# Papra_v0_6.net
KiCad netlist of a schematic drawn in EAGLE
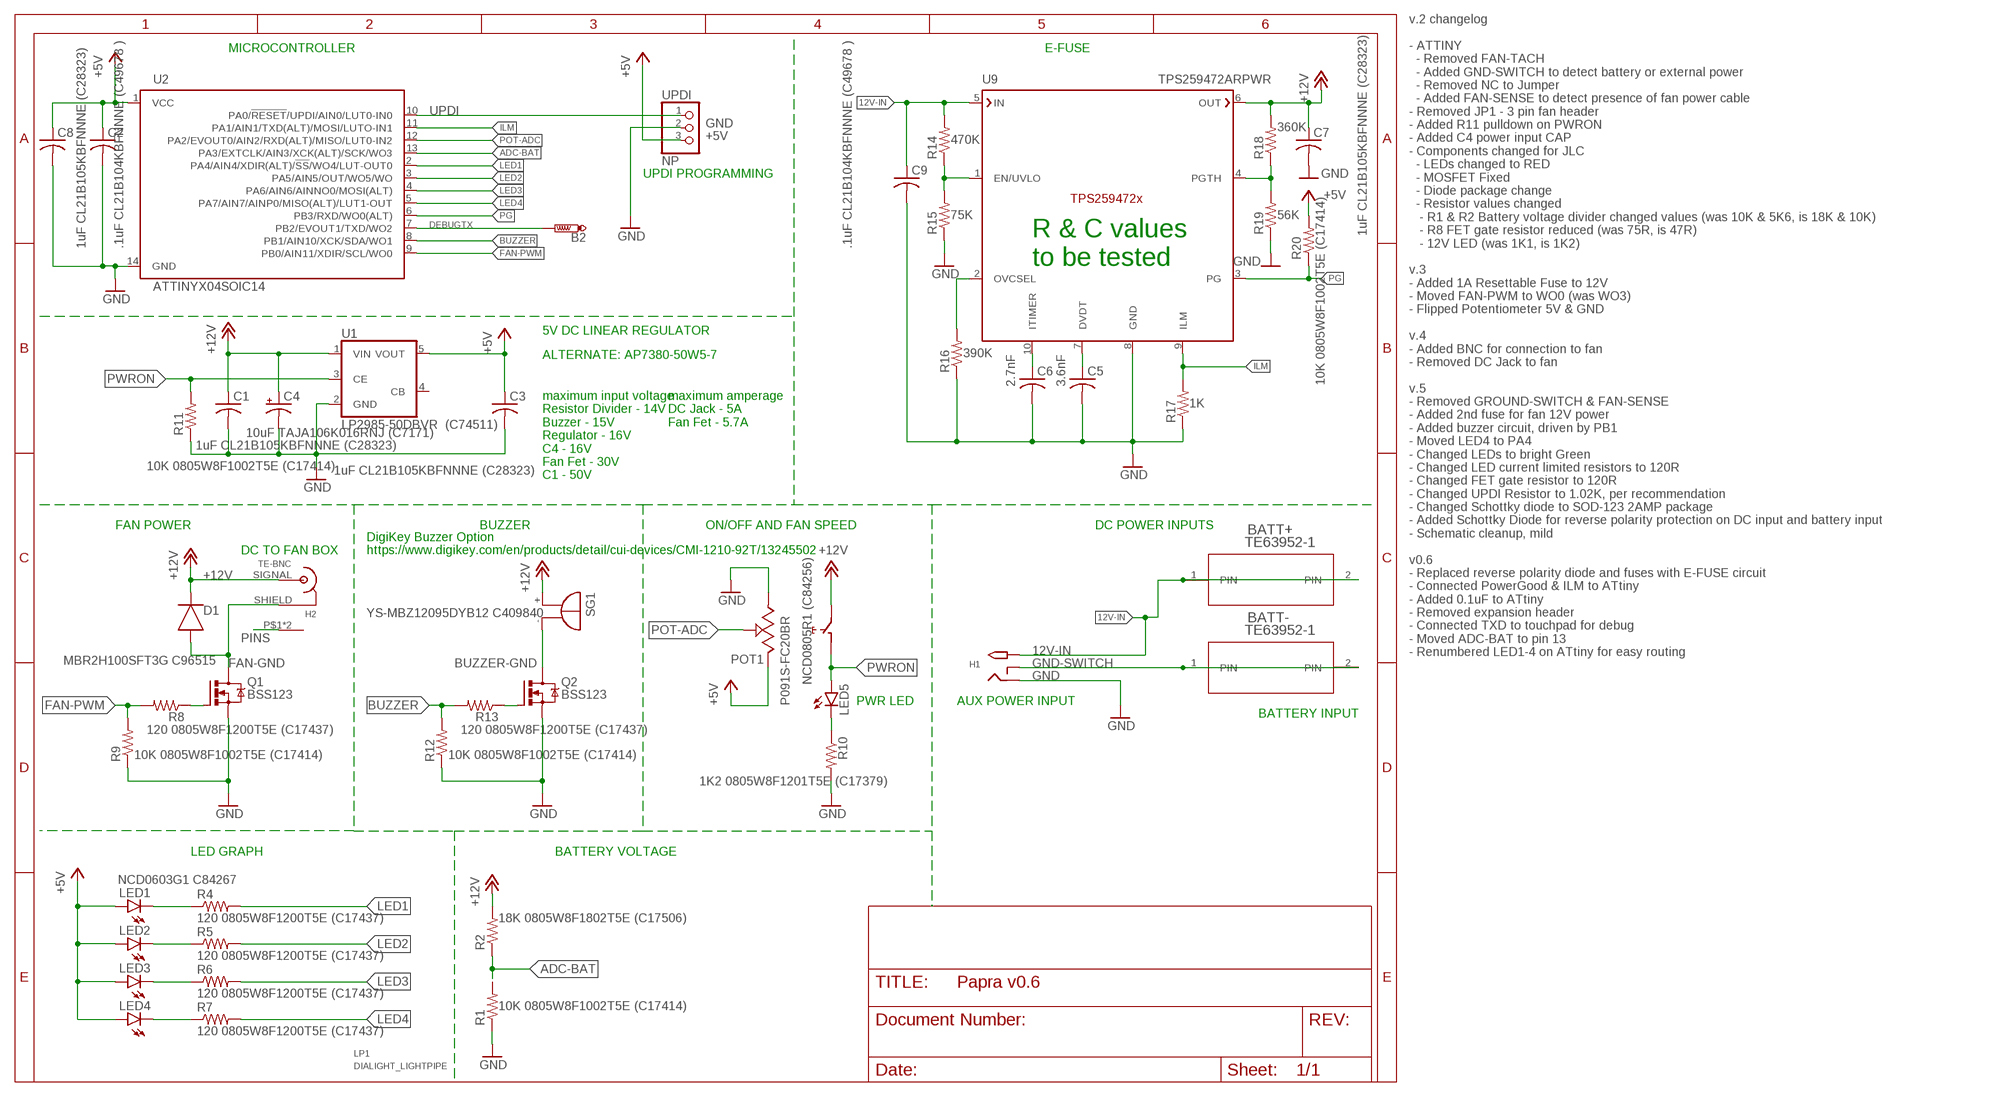
[diagram p0: schematic, sheet 1]

(export (version "E")
  (design (tool "Eeschema 10.0.6"))
  (components
    (comp (ref "B2")
      (value "PTR1PAD1-13")
      (footprint "eagle-import:P1-13")
      (libsource (lib "eagle-import") (part "PTR1PAD1-13"))
    )
    (comp (ref "BATT+")
      (value "TE63952-1")
      (footprint "eagle-import:TE63952-1")
      (libsource (lib "eagle-import") (part "TE63952-1"))
    )
    (comp (ref "BATT-")
      (value "TE63952-1")
      (footprint "eagle-import:TE63952-1")
      (libsource (lib "eagle-import") (part "TE63952-1"))
    )
    (comp (ref "C1")
      (value "1uF CL21B105KBFNNNE (C28323)")
      (footprint "eagle-import:C0805")
      (libsource (lib "eagle-import") (part "C-USC0805"))
    )
    (comp (ref "C2")
      (value ".1uF CL21B104KBFNNNE (C49678 )")
      (footprint "eagle-import:C0805")
      (libsource (lib "eagle-import") (part "C-USC0805"))
    )
    (comp (ref "C3")
      (value "1uF CL21B105KBFNNNE (C28323)")
      (footprint "eagle-import:C0805")
      (libsource (lib "eagle-import") (part "C-USC0805"))
    )
    (comp (ref "C4")
      (value "10uF TAJA106K016RNJ (C7171)")
      (footprint "eagle-import:A_3216-18R")
      (libsource (lib "eagle-import") (part "CPOL-USA/3216-18R"))
    )
    (comp (ref "C5")
      (value "3.6nF")
      (footprint "eagle-import:C0805")
      (libsource (lib "eagle-import") (part "C-USC0805"))
    )
    (comp (ref "C6")
      (value "2.7nF")
      (footprint "eagle-import:C0805")
      (libsource (lib "eagle-import") (part "C-USC0805"))
    )
    (comp (ref "C7")
      (value "1uF CL21B105KBFNNNE (C28323)")
      (footprint "eagle-import:C0805")
      (libsource (lib "eagle-import") (part "C-USC0805"))
    )
    (comp (ref "C8")
      (value "1uF CL21B105KBFNNNE (C28323)")
      (footprint "eagle-import:C0805")
      (libsource (lib "eagle-import") (part "C-USC0805"))
    )
    (comp (ref "C9")
      (value ".1uF CL21B104KBFNNNE (C49678 )")
      (footprint "eagle-import:C0805")
      (libsource (lib "eagle-import") (part "C-USC0805"))
    )
    (comp (ref "D1")
      (value "MBR2H100SFT3G C96515")
      (footprint "eagle-import:SODFL3718X115")
      (libsource (lib "eagle-import") (part "DIODEDO-219-AB(SOD123F)_"))
    )
    (comp (ref "H1")
      (value "M-CUI-PJ-066A")
      (footprint "eagle-import:DCJACK-PJ-066A")
      (libsource (lib "eagle-import") (part "PJ-066A"))
    )
    (comp (ref "H2")
      (value "TE-BNC")
      (footprint "eagle-import:TE-BNC")
      (libsource (lib "eagle-import") (part "TE-BNC"))
    )
    (comp (ref "LED1")
      (value "NCD0603G1 C84267")
      (footprint "eagle-import:CHIPLED_0805")
      (libsource (lib "eagle-import") (part "LEDCHIPLED_0805"))
    )
    (comp (ref "LED2")
      (value "NCD0603G1 C84267")
      (footprint "eagle-import:CHIPLED_0805")
      (libsource (lib "eagle-import") (part "LEDCHIPLED_0805"))
    )
    (comp (ref "LED3")
      (value "NCD0603G1 C84267")
      (footprint "eagle-import:CHIPLED_0805")
      (libsource (lib "eagle-import") (part "LEDCHIPLED_0805"))
    )
    (comp (ref "LED4")
      (value "NCD0603G1 C84267")
      (footprint "eagle-import:CHIPLED_0805")
      (libsource (lib "eagle-import") (part "LEDCHIPLED_0805"))
    )
    (comp (ref "LED5")
      (value "NCD0805R1 (C84256)")
      (footprint "eagle-import:CHIPLED_0805")
      (libsource (lib "eagle-import") (part "LEDCHIPLED_0805"))
    )
    (comp (ref "LP1")
      (value "DIALIGHT_LIGHTPIPE")
      (footprint "eagle-import:DIALIGHT_5151020F__LEDS")
      (libsource (lib "eagle-import") (part "DIALIGHT_LIGHTPIPE"))
    )
    (comp (ref "POT1")
      (value "P091S-FC20BR")
      (footprint "eagle-import:P091S-FC20BR")
      (libsource (lib "eagle-import") (part "P091S-FC20BR"))
    )
    (comp (ref "Q1")
      (value "BSS123")
      (footprint "eagle-import:SOT23")
      (fields (field (name "MANUFACTURER") "ON Semiconductor") (field (name "MPN") "BSS123L"))
      (libsource (lib "eagle-import") (part "NMOSFET_-SOT23BSS123"))
    )
    (comp (ref "Q2")
      (value "BSS123")
      (footprint "eagle-import:SOT23")
      (fields (field (name "MANUFACTURER") "ON Semiconductor") (field (name "MPN") "BSS123L"))
      (libsource (lib "eagle-import") (part "NMOSFET_-SOT23BSS123"))
    )
    (comp (ref "R1")
      (value "10K 0805W8F1002T5E (C17414)")
      (footprint "eagle-import:R0805")
      (libsource (lib "eagle-import") (part "R-US_R0805"))
    )
    (comp (ref "R2")
      (value "18K 0805W8F1802T5E (C17506)")
      (footprint "eagle-import:R0805")
      (libsource (lib "eagle-import") (part "R-US_R0805"))
    )
    (comp (ref "R4")
      (value "120 0805W8F1200T5E (C17437)")
      (footprint "eagle-import:R0805")
      (libsource (lib "eagle-import") (part "R-US_R0805"))
    )
    (comp (ref "R5")
      (value "120 0805W8F1200T5E (C17437)")
      (footprint "eagle-import:R0805")
      (libsource (lib "eagle-import") (part "R-US_R0805"))
    )
    (comp (ref "R6")
      (value "120 0805W8F1200T5E (C17437)")
      (footprint "eagle-import:R0805")
      (libsource (lib "eagle-import") (part "R-US_R0805"))
    )
    (comp (ref "R7")
      (value "120 0805W8F1200T5E (C17437)")
      (footprint "eagle-import:R0805")
      (libsource (lib "eagle-import") (part "R-US_R0805"))
    )
    (comp (ref "R8")
      (value "120 0805W8F1200T5E (C17437)")
      (footprint "eagle-import:R0805")
      (libsource (lib "eagle-import") (part "R-US_R0805"))
    )
    (comp (ref "R9")
      (value "10K 0805W8F1002T5E (C17414)")
      (footprint "eagle-import:R0805")
      (libsource (lib "eagle-import") (part "R-US_R0805"))
    )
    (comp (ref "R10")
      (value "1K2 0805W8F1201T5E (C17379)")
      (footprint "eagle-import:R0805")
      (libsource (lib "eagle-import") (part "R-US_R0805"))
    )
    (comp (ref "R11")
      (value "10K 0805W8F1002T5E (C17414)")
      (footprint "eagle-import:R0805")
      (libsource (lib "eagle-import") (part "R-US_R0805"))
    )
    (comp (ref "R12")
      (value "10K 0805W8F1002T5E (C17414)")
      (footprint "eagle-import:R0805")
      (libsource (lib "eagle-import") (part "R-US_R0805"))
    )
    (comp (ref "R13")
      (value "120 0805W8F1200T5E (C17437)")
      (footprint "eagle-import:R0805")
      (libsource (lib "eagle-import") (part "R-US_R0805"))
    )
    (comp (ref "R14")
      (value "470K")
      (footprint "eagle-import:R0805")
      (libsource (lib "eagle-import") (part "R-US_R0805"))
    )
    (comp (ref "R15")
      (value "75K")
      (footprint "eagle-import:R0805")
      (libsource (lib "eagle-import") (part "R-US_R0805"))
    )
    (comp (ref "R16")
      (value "390K")
      (footprint "eagle-import:R0805")
      (libsource (lib "eagle-import") (part "R-US_R0805"))
    )
    (comp (ref "R17")
      (value "1K")
      (footprint "eagle-import:R0805")
      (libsource (lib "eagle-import") (part "R-US_R0805"))
    )
    (comp (ref "R18")
      (value "360K")
      (footprint "eagle-import:R0805")
      (libsource (lib "eagle-import") (part "R-US_R0805"))
    )
    (comp (ref "R19")
      (value "56K")
      (footprint "eagle-import:R0805")
      (libsource (lib "eagle-import") (part "R-US_R0805"))
    )
    (comp (ref "R20")
      (value "10K 0805W8F1002T5E (C17414)")
      (footprint "eagle-import:R0805")
      (libsource (lib "eagle-import") (part "R-US_R0805"))
    )
    (comp (ref "SG1")
      (value "YS-MBZ12095DYB12 C409840")
      (footprint "eagle-import:F_TMB")
      (libsource (lib "eagle-import") (part "F/TMB"))
    )
    (comp (ref "U1")
      (value "LP2985-50DBVR (C74511)")
      (footprint "eagle-import:SOT25")
      (libsource (lib "eagle-import") (part "TS520533"))
    )
    (comp (ref "U2")
      (value "ATTINYX04SOIC14")
      (footprint "eagle-import:SOIC127P600X144-14")
      (libsource (lib "eagle-import") (part "ATTINYX04SOIC14"))
    )
    (comp (ref "U9")
      (value "TPS259472ARPWR")
      (footprint "eagle-import:QFN45P200X200X100-16N")
      (libsource (lib "eagle-import") (part "TPS259472ARPWR"))
    )
    (comp (ref "UPDI")
      (value "NP")
      (footprint "eagle-import:1X03")
      (libsource (lib "eagle-import") (part "PINHD-1X3"))
    )
  )
  (nets
    (net (code "1") (name "+5V") (class "Default")
      (node (ref "C2") (pin "1") (pinfunction "1_1") (pintype "passive"))
      (node (ref "C3") (pin "1") (pinfunction "1_1") (pintype "passive"))
      (node (ref "C8") (pin "1") (pinfunction "1_1") (pintype "passive"))
      (node (ref "LED1") (pin "A") (pinfunction "A_A") (pintype "passive"))
      (node (ref "LED2") (pin "A") (pinfunction "A_A") (pintype "passive"))
      (node (ref "LED3") (pin "A") (pinfunction "A_A") (pintype "passive"))
      (node (ref "LED4") (pin "A") (pinfunction "A_A") (pintype "passive"))
      (node (ref "POT1") (pin "3") (pinfunction "3_3") (pintype "passive"))
      (node (ref "R20") (pin "2") (pinfunction "2_2") (pintype "passive"))
      (node (ref "U1") (pin "5") (pinfunction "VOUT_5") (pintype "passive"))
      (node (ref "U2") (pin "1") (pinfunction "VCC_1") (pintype "power_in"))
      (node (ref "UPDI") (pin "3") (pinfunction "3_3") (pintype "passive"))
    )
    (net (code "2") (name "+12V") (class "Default")
      (node (ref "C1") (pin "1") (pinfunction "1_1") (pintype "passive"))
      (node (ref "C4") (pin "+") (pinfunction "+_+") (pintype "passive"))
      (node (ref "C7") (pin "1") (pinfunction "1_1") (pintype "passive"))
      (node (ref "D1") (pin "1") (pinfunction "C_1") (pintype "passive"))
      (node (ref "H2") (pin "SIGNAL") (pinfunction "P1_SIGNAL") (pintype "passive"))
      (node (ref "POT1") (pin "NO") (pinfunction "5_NO") (pintype "passive"))
      (node (ref "R18") (pin "2") (pinfunction "2_2") (pintype "passive"))
      (node (ref "R2") (pin "2") (pinfunction "2_2") (pintype "passive"))
      (node (ref "SG1") (pin "+") (pinfunction "+_+") (pintype "passive"))
      (node (ref "U1") (pin "1") (pinfunction "VIN_1") (pintype "input"))
      (node (ref "U9") (pin "6") (pinfunction "OUT_6") (pintype "power_in"))
    )
    (net (code "4") (name "/BUZZER-GND") (class "Default")
      (node (ref "Q2") (pin "3") (pinfunction "D_3") (pintype "passive"))
      (node (ref "SG1") (pin "-") (pinfunction "-_-") (pintype "passive"))
    )
    (net (code "5") (name "/DEBUGTX") (class "Default")
      (node (ref "B2") (pin "TP") (pinfunction "TP_TP") (pintype "input"))
      (node (ref "U2") (pin "7") (pinfunction "PB2/EVOUT1/TXD/WO2_7") (pintype "bidirectional"))
    )
    (net (code "6") (name "/FAN-GND") (class "Default")
      (node (ref "D1") (pin "2") (pinfunction "A_2") (pintype "passive"))
      (node (ref "H2") (pin "SHIELD") (pinfunction "P2_SHIELD") (pintype "passive"))
      (node (ref "Q1") (pin "3") (pinfunction "D_3") (pintype "passive"))
    )
    (net (code "7") (name "/GND-SWITCH") (class "Default")
      (node (ref "BATT-") (pin "1") (pinfunction "PIN_1") (pintype "passive"))
      (node (ref "BATT-") (pin "2") (pinfunction "PIN_2") (pintype "passive"))
      (node (ref "H1") (pin "GNDBREAK") (pinfunction "RING_SW_GNDBREAK") (pintype "bidirectional"))
    )
    (net (code "8") (name "/PINS") (class "Default")
      (node (ref "H2") (pin "P$1") (pinfunction "P3_P$1") (pintype "passive"))
      (node (ref "H2") (pin "P$2") (pinfunction "P3_P$2") (pintype "passive"))
    )
    (net (code "9") (name "/UPDI") (class "Default")
      (node (ref "U2") (pin "10") (pinfunction "PA0/~{RESET}/UPDI/AIN0/LUT0-IN0_10") (pintype "bidirectional"))
      (node (ref "UPDI") (pin "1") (pinfunction "1_1") (pintype "passive"))
    )
    (net (code "10") (name "12V-IN") (class "Default")
      (node (ref "BATT+") (pin "1") (pinfunction "PIN_1") (pintype "passive"))
      (node (ref "BATT+") (pin "2") (pinfunction "PIN_2") (pintype "passive"))
      (node (ref "C9") (pin "1") (pinfunction "1_1") (pintype "passive"))
      (node (ref "H1") (pin "PWR") (pinfunction "TIP_PWR") (pintype "bidirectional"))
      (node (ref "R14") (pin "2") (pinfunction "2_2") (pintype "passive"))
      (node (ref "U9") (pin "5") (pinfunction "IN_5") (pintype "power_in"))
    )
    (net (code "11") (name "ADC-BAT") (class "Default")
      (node (ref "R1") (pin "2") (pinfunction "2_2") (pintype "passive"))
      (node (ref "R2") (pin "1") (pinfunction "1_1") (pintype "passive"))
      (node (ref "U2") (pin "13") (pinfunction "PA3/EXTCLK/AIN3/XCK(ALT)/SCK/WO3_13") (pintype "bidirectional"))
    )
    (net (code "12") (name "BUZZER") (class "Default")
      (node (ref "R12") (pin "2") (pinfunction "2_2") (pintype "passive"))
      (node (ref "R13") (pin "2") (pinfunction "2_2") (pintype "passive"))
      (node (ref "U2") (pin "8") (pinfunction "PB1/AIN10/XCK/SDA/WO1_8") (pintype "bidirectional"))
    )
    (net (code "13") (name "FAN-PWM") (class "Default")
      (node (ref "R8") (pin "2") (pinfunction "2_2") (pintype "passive"))
      (node (ref "R9") (pin "2") (pinfunction "2_2") (pintype "passive"))
      (node (ref "U2") (pin "9") (pinfunction "PB0/AIN11/XDIR/SCL/WO0_9") (pintype "bidirectional"))
    )
    (net (code "14") (name "GND") (class "Default")
      (node (ref "C1") (pin "2") (pinfunction "2_2") (pintype "passive"))
      (node (ref "C2") (pin "2") (pinfunction "2_2") (pintype "passive"))
      (node (ref "C3") (pin "2") (pinfunction "2_2") (pintype "passive"))
      (node (ref "C4") (pin "-") (pinfunction "-_-") (pintype "passive"))
      (node (ref "C5") (pin "2") (pinfunction "2_2") (pintype "passive"))
      (node (ref "C6") (pin "2") (pinfunction "2_2") (pintype "passive"))
      (node (ref "C7") (pin "2") (pinfunction "2_2") (pintype "passive"))
      (node (ref "C8") (pin "2") (pinfunction "2_2") (pintype "passive"))
      (node (ref "C9") (pin "2") (pinfunction "2_2") (pintype "passive"))
      (node (ref "H1") (pin "GND") (pinfunction "RING_GND") (pintype "bidirectional"))
      (node (ref "POT1") (pin "1") (pinfunction "1_1") (pintype "passive"))
      (node (ref "Q1") (pin "2") (pinfunction "S_2") (pintype "passive"))
      (node (ref "Q2") (pin "2") (pinfunction "S_2") (pintype "passive"))
      (node (ref "R1") (pin "1") (pinfunction "1_1") (pintype "passive"))
      (node (ref "R10") (pin "2") (pinfunction "2_2") (pintype "passive"))
      (node (ref "R11") (pin "1") (pinfunction "1_1") (pintype "passive"))
      (node (ref "R12") (pin "1") (pinfunction "1_1") (pintype "passive"))
      (node (ref "R15") (pin "1") (pinfunction "1_1") (pintype "passive"))
      (node (ref "R16") (pin "1") (pinfunction "1_1") (pintype "passive"))
      (node (ref "R17") (pin "1") (pinfunction "1_1") (pintype "passive"))
      (node (ref "R19") (pin "1") (pinfunction "1_1") (pintype "passive"))
      (node (ref "R9") (pin "1") (pinfunction "1_1") (pintype "passive"))
      (node (ref "U1") (pin "2") (pinfunction "GND_2") (pintype "passive"))
      (node (ref "U2") (pin "14") (pinfunction "GND_14") (pintype "power_in"))
      (node (ref "U9") (pin "8") (pinfunction "GND_8") (pintype "power_in"))
      (node (ref "UPDI") (pin "2") (pinfunction "2_2") (pintype "passive"))
    )
    (net (code "15") (name "ILM") (class "Default")
      (node (ref "R17") (pin "2") (pinfunction "2_2") (pintype "passive"))
      (node (ref "U2") (pin "11") (pinfunction "PA1/AIN1/TXD(ALT)/MOSI/LUTO-IN1_11") (pintype "bidirectional"))
      (node (ref "U9") (pin "9") (pinfunction "ILM_9") (pintype "output"))
    )
    (net (code "16") (name "LED1") (class "Default")
      (node (ref "R4") (pin "2") (pinfunction "2_2") (pintype "passive"))
      (node (ref "U2") (pin "2") (pinfunction "PA4/AIN4/XDIR(ALT)/~{SS}/WO4/LUT-OUT0_2") (pintype "bidirectional"))
    )
    (net (code "17") (name "LED2") (class "Default")
      (node (ref "R5") (pin "2") (pinfunction "2_2") (pintype "passive"))
      (node (ref "U2") (pin "3") (pinfunction "PA5/AIN5/OUT/WO5/WO_3") (pintype "bidirectional"))
    )
    (net (code "18") (name "LED3") (class "Default")
      (node (ref "R6") (pin "2") (pinfunction "2_2") (pintype "passive"))
      (node (ref "U2") (pin "4") (pinfunction "PA6/AIN6/AINNO0/MOSI(ALT)_4") (pintype "bidirectional"))
    )
    (net (code "19") (name "LED4") (class "Default")
      (node (ref "R7") (pin "2") (pinfunction "2_2") (pintype "passive"))
      (node (ref "U2") (pin "5") (pinfunction "PA7/AIN7/AINP0/MISO(ALT)/LUT1-OUT_5") (pintype "bidirectional"))
    )
    (net (code "20") (name "Net-(LED1-PadC)") (class "Default")
      (node (ref "LED1") (pin "C") (pinfunction "C_C") (pintype "passive"))
      (node (ref "R4") (pin "1") (pinfunction "1_1") (pintype "passive"))
    )
    (net (code "21") (name "Net-(LED2-PadC)") (class "Default")
      (node (ref "LED2") (pin "C") (pinfunction "C_C") (pintype "passive"))
      (node (ref "R5") (pin "1") (pinfunction "1_1") (pintype "passive"))
    )
    (net (code "22") (name "Net-(LED3-PadC)") (class "Default")
      (node (ref "LED3") (pin "C") (pinfunction "C_C") (pintype "passive"))
      (node (ref "R6") (pin "1") (pinfunction "1_1") (pintype "passive"))
    )
    (net (code "23") (name "Net-(LED4-PadC)") (class "Default")
      (node (ref "LED4") (pin "C") (pinfunction "C_C") (pintype "passive"))
      (node (ref "R7") (pin "1") (pinfunction "1_1") (pintype "passive"))
    )
    (net (code "24") (name "Net-(LED5-PadC)") (class "Default")
      (node (ref "LED5") (pin "C") (pinfunction "C_C") (pintype "passive"))
      (node (ref "R10") (pin "1") (pinfunction "1_1") (pintype "passive"))
    )
    (net (code "25") (name "Net-(Q1-G)") (class "Default")
      (node (ref "Q1") (pin "1") (pinfunction "G_1") (pintype "passive"))
      (node (ref "R8") (pin "1") (pinfunction "1_1") (pintype "passive"))
    )
    (net (code "26") (name "Net-(Q2-G)") (class "Default")
      (node (ref "Q2") (pin "1") (pinfunction "G_1") (pintype "passive"))
      (node (ref "R13") (pin "1") (pinfunction "1_1") (pintype "passive"))
    )
    (net (code "27") (name "Net-(U9-DVDT)") (class "Default")
      (node (ref "C5") (pin "1") (pinfunction "1_1") (pintype "passive"))
      (node (ref "U9") (pin "7") (pinfunction "DVDT_7") (pintype "output"))
    )
    (net (code "28") (name "Net-(U9-EN{slash}UVLO)") (class "Default")
      (node (ref "R14") (pin "1") (pinfunction "1_1") (pintype "passive"))
      (node (ref "R15") (pin "2") (pinfunction "2_2") (pintype "passive"))
      (node (ref "U9") (pin "1") (pinfunction "EN/UVLO_1") (pintype "input"))
    )
    (net (code "29") (name "Net-(U9-ITIMER)") (class "Default")
      (node (ref "C6") (pin "1") (pinfunction "1_1") (pintype "passive"))
      (node (ref "U9") (pin "10") (pinfunction "ITIMER_10") (pintype "output"))
    )
    (net (code "30") (name "Net-(U9-OVCSEL)") (class "Default")
      (node (ref "R16") (pin "2") (pinfunction "2_2") (pintype "passive"))
      (node (ref "U9") (pin "2") (pinfunction "OVCSEL_2") (pintype "input"))
    )
    (net (code "31") (name "Net-(U9-PGTH)") (class "Default")
      (node (ref "R18") (pin "1") (pinfunction "1_1") (pintype "passive"))
      (node (ref "R19") (pin "2") (pinfunction "2_2") (pintype "passive"))
      (node (ref "U9") (pin "4") (pinfunction "PGTH_4") (pintype "input"))
    )
    (net (code "32") (name "PG") (class "Default")
      (node (ref "R20") (pin "1") (pinfunction "1_1") (pintype "passive"))
      (node (ref "U2") (pin "6") (pinfunction "PB3/RXD/WO0(ALT)_6") (pintype "bidirectional"))
      (node (ref "U9") (pin "3") (pinfunction "PG_3") (pintype "output"))
    )
    (net (code "33") (name "POT-ADC") (class "Default")
      (node (ref "POT1") (pin "2") (pinfunction "2_2") (pintype "passive"))
      (node (ref "U2") (pin "12") (pinfunction "PA2/EVOUT0/AIN2/RXD(ALT)/MISO/LUT0-IN2_12") (pintype "bidirectional"))
    )
    (net (code "34") (name "PWRON") (class "Default")
      (node (ref "LED5") (pin "A") (pinfunction "A_A") (pintype "passive"))
      (node (ref "POT1") (pin "COM") (pinfunction "4_COM") (pintype "passive"))
      (node (ref "R11") (pin "2") (pinfunction "2_2") (pintype "passive"))
      (node (ref "U1") (pin "3") (pinfunction "CE_3") (pintype "input"))
    )
    (net (code "35") (name "unconnected-(U1-CB-Pad4)") (class "Default")
      (node (ref "U1") (pin "4") (pinfunction "CB_4") (pintype "input"))
    )
  )
)
